# MainPCB.net
KiCad netlist of a schematic drawn in EAGLE
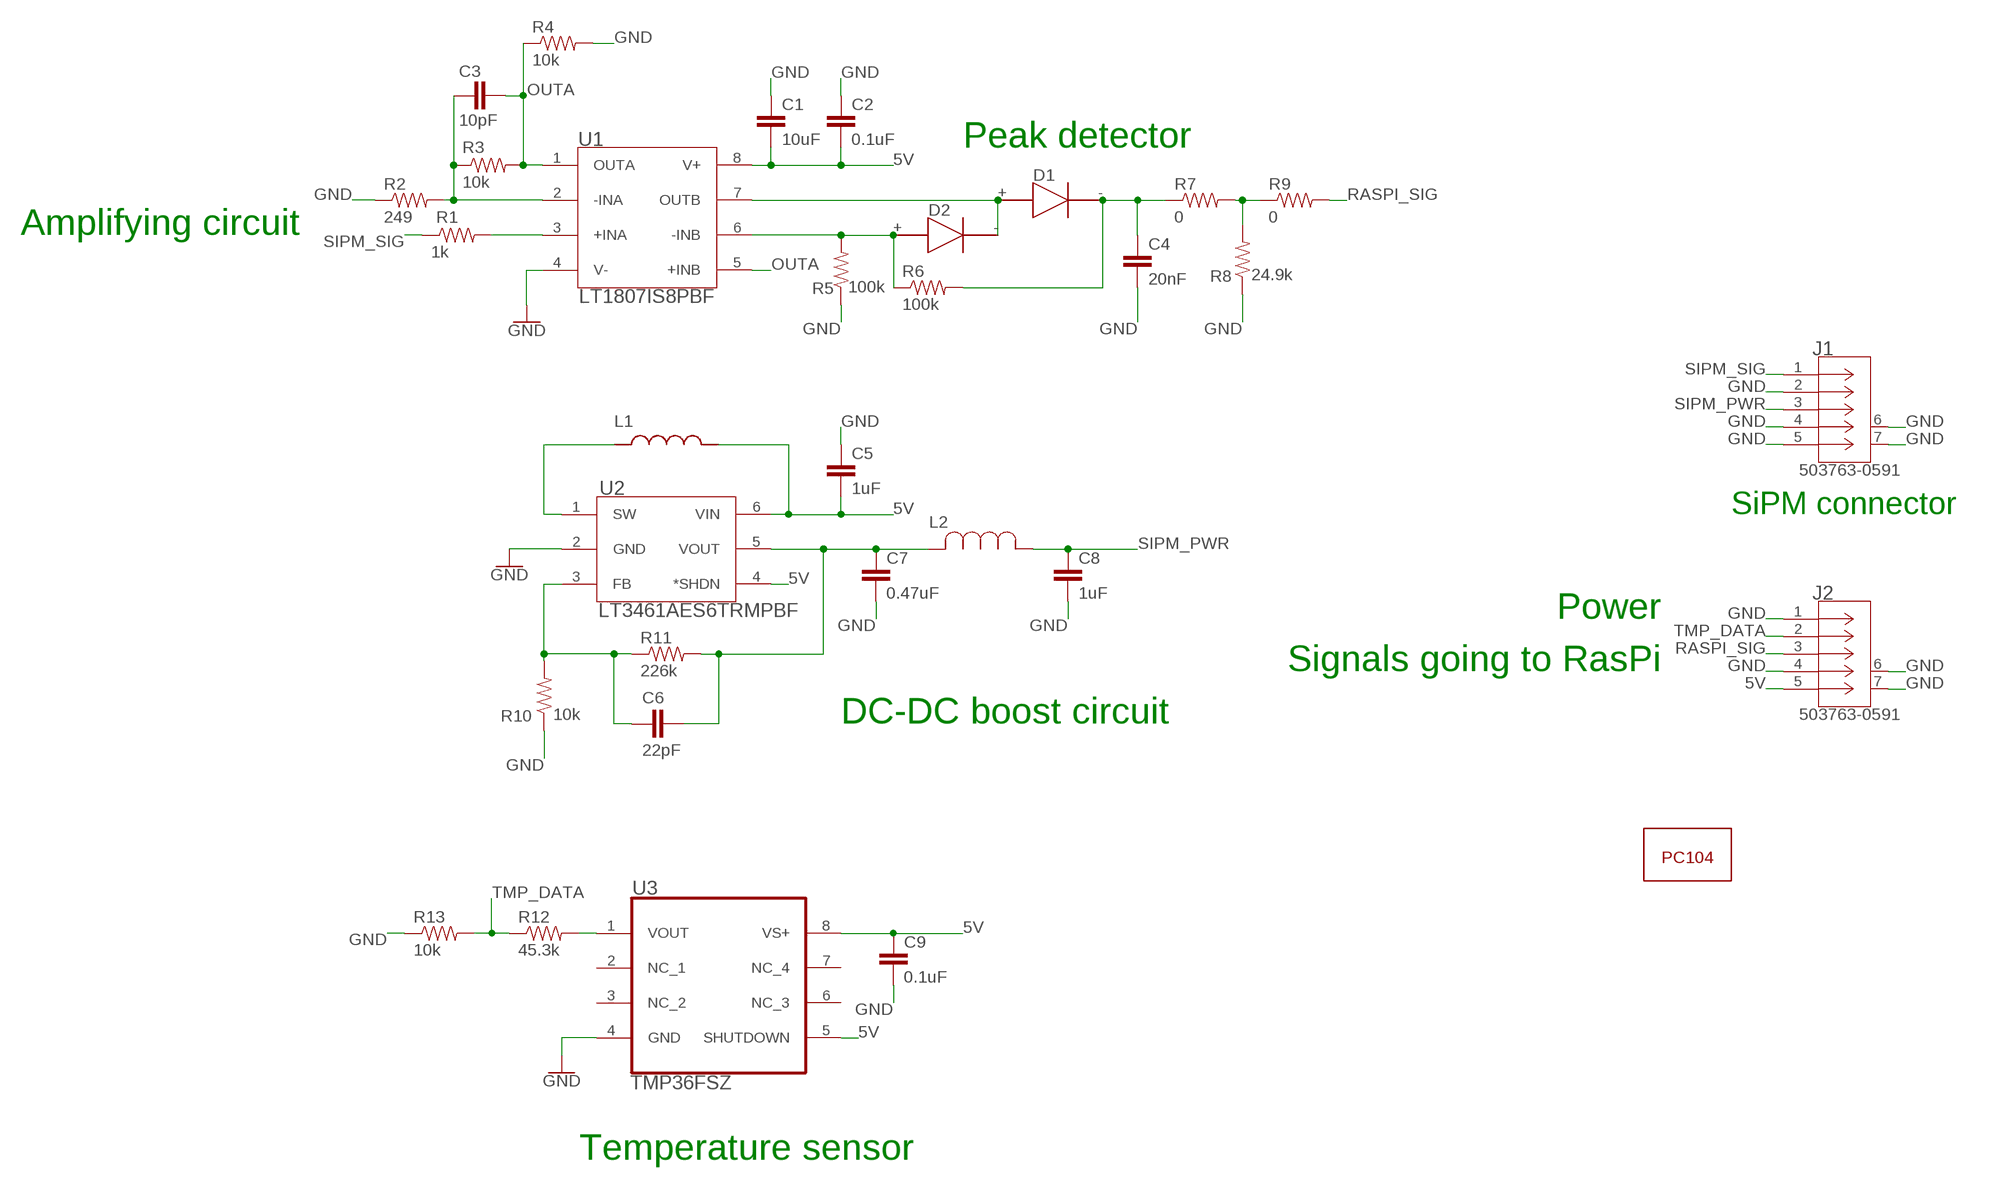
[diagram p0: schematic, sheet 1]

(export (version "E")
  (design (tool "Eeschema 10.0.6"))
  (components
    (comp (ref "C1")
      (value "10uF")
      (footprint "eagle-import:0805")
      (libsource (lib "eagle-import") (part "CAP0805"))
    )
    (comp (ref "C2")
      (value "0.1uF")
      (footprint "eagle-import:0805")
      (libsource (lib "eagle-import") (part "CAP0805"))
    )
    (comp (ref "C3")
      (value "10pF")
      (footprint "eagle-import:0805")
      (libsource (lib "eagle-import") (part "CAP0805"))
    )
    (comp (ref "C4")
      (value "20nF")
      (footprint "eagle-import:0805")
      (libsource (lib "eagle-import") (part "CAP0805"))
    )
    (comp (ref "C5")
      (value "1uF")
      (footprint "eagle-import:0805")
      (libsource (lib "eagle-import") (part "CAP0805"))
    )
    (comp (ref "C6")
      (value "22pF")
      (footprint "eagle-import:0805")
      (libsource (lib "eagle-import") (part "CAP0805"))
    )
    (comp (ref "C7")
      (value "0.47uF")
      (footprint "eagle-import:0805")
      (libsource (lib "eagle-import") (part "CAP0805"))
    )
    (comp (ref "C8")
      (value "1uF")
      (footprint "eagle-import:0805")
      (libsource (lib "eagle-import") (part "CAP0805"))
    )
    (comp (ref "C9")
      (value "0.1uF")
      (footprint "eagle-import:0805")
      (libsource (lib "eagle-import") (part "CAP0805"))
    )
    (comp (ref "D1")
      (value "RBR1VWM40ATR")
      (footprint "eagle-import:RBR1VWM40ATR")
      (libsource (lib "eagle-import") (part "RBR1VWM40ATR"))
    )
    (comp (ref "D2")
      (value "RBR1VWM40ATR")
      (footprint "eagle-import:RBR1VWM40ATR")
      (libsource (lib "eagle-import") (part "RBR1VWM40ATR"))
    )
    (comp (ref "J1")
      (value "503763-0591")
      (footprint "eagle-import:CONN_5037630591_MOL")
      (fields (field (name "COPYRIGHT") "Copyright (C) 2018 Accelerated Designs. All rights reserved"))
      (libsource (lib "eagle-import") (part "503763-0591"))
    )
    (comp (ref "J2")
      (value "503763-0591")
      (footprint "eagle-import:CONN_5037630591_MOL")
      (fields (field (name "COPYRIGHT") "Copyright (C) 2018 Accelerated Designs. All rights reserved"))
      (libsource (lib "eagle-import") (part "503763-0591"))
    )
    (comp (ref "L1")
      (value "47uH")
      (footprint "eagle-import:IND_LQH32CN470K53L")
      (fields
        (field (name "DIGI-KEY_PART_NUMBER") "490-4063-1-ND")
        (field (name "MF") "Murata")
        (field (name "MP") "LQH32CN470K53L")
      )
      (libsource (lib "eagle-import") (part "LQH32CN470K53L"))
    )
    (comp (ref "L2")
      (value "BK2125LM252-T")
      (footprint "eagle-import:BK2125HS_TAY")
      (fields (field (name "COPYRIGHT") "Copyright (C) 2021 Ultra Librarian. All rights reserved."))
      (libsource (lib "eagle-import") (part "BK2125LM252-T"))
    )
    (comp (ref "R1")
      (value "1k")
      (footprint "eagle-import:0805")
      (libsource (lib "eagle-import") (part "RESISTOR0805-RES"))
    )
    (comp (ref "R2")
      (value "249")
      (footprint "eagle-import:0805")
      (libsource (lib "eagle-import") (part "RESISTOR0805-RES"))
    )
    (comp (ref "R3")
      (value "10k")
      (footprint "eagle-import:0805")
      (libsource (lib "eagle-import") (part "RESISTOR0805-RES"))
    )
    (comp (ref "R4")
      (value "10k")
      (footprint "eagle-import:0805")
      (libsource (lib "eagle-import") (part "RESISTOR0805-RES"))
    )
    (comp (ref "R5")
      (value "100k")
      (footprint "eagle-import:0805")
      (libsource (lib "eagle-import") (part "RESISTOR0805-RES"))
    )
    (comp (ref "R6")
      (value "100k")
      (footprint "eagle-import:0805")
      (libsource (lib "eagle-import") (part "RESISTOR0805-RES"))
    )
    (comp (ref "R7")
      (value "0")
      (footprint "eagle-import:0805")
      (libsource (lib "eagle-import") (part "RESISTOR0805-RES"))
    )
    (comp (ref "R8")
      (value "24.9k")
      (footprint "eagle-import:0805")
      (libsource (lib "eagle-import") (part "RESISTOR0805-RES"))
    )
    (comp (ref "R9")
      (value "0")
      (footprint "eagle-import:0805")
      (libsource (lib "eagle-import") (part "RESISTOR0805-RES"))
    )
    (comp (ref "R10")
      (value "10k")
      (footprint "eagle-import:0805")
      (libsource (lib "eagle-import") (part "RESISTOR0805-RES"))
    )
    (comp (ref "R11")
      (value "226k")
      (footprint "eagle-import:0805")
      (libsource (lib "eagle-import") (part "RESISTOR0805-RES"))
    )
    (comp (ref "R12")
      (value "45.3k")
      (footprint "eagle-import:0805")
      (libsource (lib "eagle-import") (part "RESISTOR0805-RES"))
    )
    (comp (ref "R13")
      (value "10k")
      (footprint "eagle-import:0805")
      (libsource (lib "eagle-import") (part "RESISTOR0805-RES"))
    )
    (comp (ref "U$1")
      (value "PC104_WCONN_DETECTOR")
      (footprint "eagle-import:PC104_WCONN_DETECTOR")
      (libsource (lib "eagle-import") (part "PC104_WCONN_DETECTOR"))
    )
    (comp (ref "U1")
      (value "LT1807IS8PBF")
      (footprint "eagle-import:MSOP-8_MS_LIT")
      (fields
        (field (name "MANUFACTURER_PART_NUMBER") "LT1807IS8#PBF")
        (field (name "COPYRIGHT") "Copyright (C) 2021 Ultra Librarian. All rights reserved.")
      )
      (libsource (lib "eagle-import") (part "LT1807IS8PBF"))
    )
    (comp (ref "U2")
      (value "LT3461AES6TRMPBF")
      (footprint "eagle-import:TSOT-23_S6")
      (fields
        (field (name "DIGI-KEY_PART_NUMBER") "LT3461AES6#TRMPBFCT-ND")
        (field (name "MF") "Analog Devices")
        (field (name "MP") "LT3461AES6#TRMPBF")
      )
      (libsource (lib "eagle-import") (part "LT3461AES6TRMPBF"))
    )
    (comp (ref "U3")
      (value "TMP36FSZ")
      (footprint "eagle-import:SOIC127P600X175-8N")
      (libsource (lib "eagle-import") (part "TMP36GSZ"))
    )
  )
  (nets
    (net (code "1") (name "/5V") (class "Default")
      (node (ref "C1") (pin "2") (pinfunction "2_2") (pintype "passive"))
      (node (ref "C2") (pin "2") (pinfunction "2_2") (pintype "passive"))
      (node (ref "C5") (pin "2") (pinfunction "2_2") (pintype "passive"))
      (node (ref "C9") (pin "1") (pinfunction "1_1") (pintype "passive"))
      (node (ref "J2") (pin "5") (pinfunction "5_5") (pintype "passive"))
      (node (ref "L1") (pin "2") (pinfunction "2_2") (pintype "passive"))
      (node (ref "U1") (pin "8") (pinfunction "V+_8") (pintype "power_in"))
      (node (ref "U2") (pin "4") (pinfunction "*SHDN_4") (pintype "passive"))
      (node (ref "U2") (pin "6") (pinfunction "VIN_6") (pintype "input"))
      (node (ref "U3") (pin "5") (pinfunction "SHUTDOWN_5") (pintype "passive"))
      (node (ref "U3") (pin "8") (pinfunction "VS+_8") (pintype "power_in"))
    )
    (net (code "2") (name "/OUTA") (class "Default")
      (node (ref "C3") (pin "2") (pinfunction "2_2") (pintype "passive"))
      (node (ref "R3") (pin "2") (pinfunction "2_2") (pintype "passive"))
      (node (ref "R4") (pin "1") (pinfunction "1_1") (pintype "passive"))
      (node (ref "U1") (pin "1") (pinfunction "OUTA_1") (pintype "output"))
      (node (ref "U1") (pin "5") (pinfunction "+INB_5") (pintype "input"))
    )
    (net (code "3") (name "/RASPI_SIG") (class "Default")
      (node (ref "J2") (pin "3") (pinfunction "3_3") (pintype "passive"))
      (node (ref "R9") (pin "2") (pinfunction "2_2") (pintype "passive"))
    )
    (net (code "4") (name "/SIPM_PWR") (class "Default")
      (node (ref "C8") (pin "1") (pinfunction "1_1") (pintype "passive"))
      (node (ref "J1") (pin "3") (pinfunction "3_3") (pintype "passive"))
      (node (ref "L2") (pin "1") (pinfunction "1_1") (pintype "passive"))
    )
    (net (code "5") (name "/SIPM_SIG") (class "Default")
      (node (ref "J1") (pin "1") (pinfunction "1_1") (pintype "passive"))
      (node (ref "R1") (pin "1") (pinfunction "1_1") (pintype "passive"))
    )
    (net (code "6") (name "/TMP_DATA") (class "Default")
      (node (ref "J2") (pin "2") (pinfunction "2_2") (pintype "passive"))
      (node (ref "R12") (pin "1") (pinfunction "1_1") (pintype "passive"))
      (node (ref "R13") (pin "2") (pinfunction "2_2") (pintype "passive"))
    )
    (net (code "7") (name "GND") (class "Default")
      (node (ref "C1") (pin "1") (pinfunction "1_1") (pintype "passive"))
      (node (ref "C2") (pin "1") (pinfunction "1_1") (pintype "passive"))
      (node (ref "C4") (pin "2") (pinfunction "2_2") (pintype "passive"))
      (node (ref "C5") (pin "1") (pinfunction "1_1") (pintype "passive"))
      (node (ref "C7") (pin "2") (pinfunction "2_2") (pintype "passive"))
      (node (ref "C8") (pin "2") (pinfunction "2_2") (pintype "passive"))
      (node (ref "C9") (pin "2") (pinfunction "2_2") (pintype "passive"))
      (node (ref "J1") (pin "2") (pinfunction "2_2") (pintype "passive"))
      (node (ref "J1") (pin "4") (pinfunction "4_4") (pintype "passive"))
      (node (ref "J1") (pin "5") (pinfunction "5_5") (pintype "passive"))
      (node (ref "J1") (pin "6") (pinfunction "6_6") (pintype "bidirectional"))
      (node (ref "J1") (pin "7") (pinfunction "7_7") (pintype "bidirectional"))
      (node (ref "J2") (pin "1") (pinfunction "1_1") (pintype "passive"))
      (node (ref "J2") (pin "4") (pinfunction "4_4") (pintype "passive"))
      (node (ref "J2") (pin "6") (pinfunction "6_6") (pintype "bidirectional"))
      (node (ref "J2") (pin "7") (pinfunction "7_7") (pintype "bidirectional"))
      (node (ref "R10") (pin "1") (pinfunction "1_1") (pintype "passive"))
      (node (ref "R13") (pin "1") (pinfunction "1_1") (pintype "passive"))
      (node (ref "R2") (pin "1") (pinfunction "1_1") (pintype "passive"))
      (node (ref "R4") (pin "2") (pinfunction "2_2") (pintype "passive"))
      (node (ref "R5") (pin "1") (pinfunction "1_1") (pintype "passive"))
      (node (ref "R8") (pin "1") (pinfunction "1_1") (pintype "passive"))
      (node (ref "U1") (pin "4") (pinfunction "V-_4") (pintype "power_in"))
      (node (ref "U2") (pin "2") (pinfunction "GND_2") (pintype "power_in"))
      (node (ref "U3") (pin "4") (pinfunction "GND_4") (pintype "passive"))
    )
    (net (code "8") (name "Net-(C4-Pad1)") (class "Default")
      (node (ref "C4") (pin "1") (pinfunction "1_1") (pintype "passive"))
      (node (ref "D1") (pin "-") (pinfunction "-_-") (pintype "bidirectional"))
      (node (ref "R6") (pin "2") (pinfunction "2_2") (pintype "passive"))
      (node (ref "R7") (pin "1") (pinfunction "1_1") (pintype "passive"))
    )
    (net (code "9") (name "Net-(R7-Pad2)") (class "Default")
      (node (ref "R7") (pin "2") (pinfunction "2_2") (pintype "passive"))
      (node (ref "R8") (pin "2") (pinfunction "2_2") (pintype "passive"))
      (node (ref "R9") (pin "1") (pinfunction "1_1") (pintype "passive"))
    )
    (net (code "10") (name "Net-(U1-+INA)") (class "Default")
      (node (ref "R1") (pin "2") (pinfunction "2_2") (pintype "passive"))
      (node (ref "U1") (pin "3") (pinfunction "+INA_3") (pintype "input"))
    )
    (net (code "11") (name "Net-(U1--INA)") (class "Default")
      (node (ref "C3") (pin "1") (pinfunction "1_1") (pintype "passive"))
      (node (ref "R2") (pin "2") (pinfunction "2_2") (pintype "passive"))
      (node (ref "R3") (pin "1") (pinfunction "1_1") (pintype "passive"))
      (node (ref "U1") (pin "2") (pinfunction "-INA_2") (pintype "input"))
    )
    (net (code "12") (name "Net-(U1--INB)") (class "Default")
      (node (ref "D2") (pin "+") (pinfunction "+_+") (pintype "bidirectional"))
      (node (ref "R5") (pin "2") (pinfunction "2_2") (pintype "passive"))
      (node (ref "R6") (pin "1") (pinfunction "1_1") (pintype "passive"))
      (node (ref "U1") (pin "6") (pinfunction "-INB_6") (pintype "input"))
    )
    (net (code "13") (name "Net-(U1-OUTB)") (class "Default")
      (node (ref "D1") (pin "+") (pinfunction "+_+") (pintype "bidirectional"))
      (node (ref "D2") (pin "-") (pinfunction "-_-") (pintype "bidirectional"))
      (node (ref "U1") (pin "7") (pinfunction "OUTB_7") (pintype "output"))
    )
    (net (code "14") (name "Net-(U2-FB)") (class "Default")
      (node (ref "C6") (pin "1") (pinfunction "1_1") (pintype "passive"))
      (node (ref "R10") (pin "2") (pinfunction "2_2") (pintype "passive"))
      (node (ref "R11") (pin "1") (pinfunction "1_1") (pintype "passive"))
      (node (ref "U2") (pin "3") (pinfunction "FB_3") (pintype "passive"))
    )
    (net (code "15") (name "Net-(U2-SW)") (class "Default")
      (node (ref "L1") (pin "1") (pinfunction "1_1") (pintype "passive"))
      (node (ref "U2") (pin "1") (pinfunction "SW_1") (pintype "passive"))
    )
    (net (code "16") (name "Net-(U2-VOUT)") (class "Default")
      (node (ref "C6") (pin "2") (pinfunction "2_2") (pintype "passive"))
      (node (ref "C7") (pin "1") (pinfunction "1_1") (pintype "passive"))
      (node (ref "L2") (pin "2") (pinfunction "2_2") (pintype "passive"))
      (node (ref "R11") (pin "2") (pinfunction "2_2") (pintype "passive"))
      (node (ref "U2") (pin "5") (pinfunction "VOUT_5") (pintype "output"))
    )
    (net (code "17") (name "Net-(U3-VOUT)") (class "Default")
      (node (ref "R12") (pin "2") (pinfunction "2_2") (pintype "passive"))
      (node (ref "U3") (pin "1") (pinfunction "VOUT_1") (pintype "passive"))
    )
    (net (code "18") (name "unconnected-(U3-NC_1-Pad2)") (class "Default")
      (node (ref "U3") (pin "2") (pinfunction "NC_1_2") (pintype "passive"))
    )
    (net (code "19") (name "unconnected-(U3-NC_2-Pad3)") (class "Default")
      (node (ref "U3") (pin "3") (pinfunction "NC_2_3") (pintype "passive"))
    )
    (net (code "20") (name "unconnected-(U3-NC_3-Pad6)") (class "Default")
      (node (ref "U3") (pin "6") (pinfunction "NC_3_6") (pintype "passive"))
    )
    (net (code "21") (name "unconnected-(U3-NC_4-Pad7)") (class "Default")
      (node (ref "U3") (pin "7") (pinfunction "NC_4_7") (pintype "passive"))
    )
  )
)
